# picaxe_prog_breakout.net
KiCad netlist of a schematic drawn in EAGLE
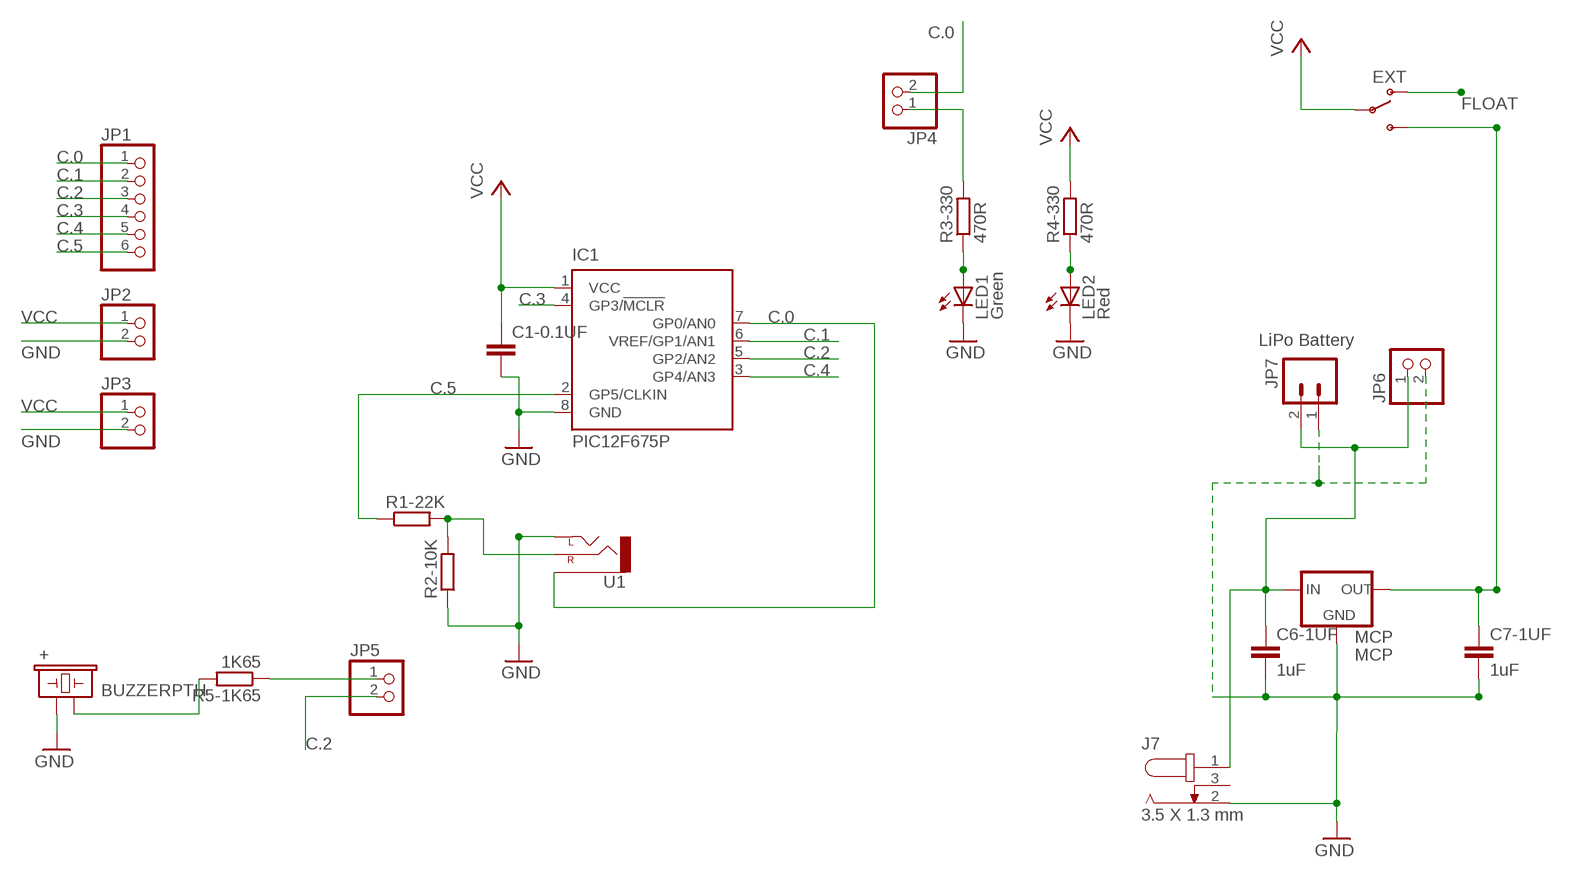
[diagram p0: schematic, sheet 1]

(export (version "E")
  (design (tool "Eeschema 10.0.6"))
  (components
    (comp (ref "+")
      (value "BUZZERPTH")
      (footprint "eagle-import:BUZZER-12MM")
      (libsource (lib "eagle-import") (part "BUZZERPTH"))
    )
    (comp (ref "C1-0.1UF")
      (value "C-EU025-025X050")
      (footprint "eagle-import:C025-025X050")
      (libsource (lib "eagle-import") (part "C-EU025-025X050"))
    )
    (comp (ref "C6-1UF")
      (value "1uF")
      (footprint "eagle-import:C050-025X075")
      (libsource (lib "eagle-import") (part "C-EU050-025X075"))
    )
    (comp (ref "C7-1UF")
      (value "1uF")
      (footprint "eagle-import:C050-025X075")
      (libsource (lib "eagle-import") (part "C-EU050-025X075"))
    )
    (comp (ref "IC1")
      (value "PIC12F675P")
      (footprint "eagle-import:DIL8")
      (fields (field (name "MF") "MICROCHIP") (field (name "MPN") "PIC12F675-E/P"))
      (libsource (lib "eagle-import") (part "PIC12F675P"))
    )
    (comp (ref "J7")
      (value "3.5 X 1.3 mm")
      (footprint "eagle-import:3.5X1.3MM_DC_JACK")
      (libsource (lib "eagle-import") (part "DC_JACK_3.5X1.3MM"))
    )
    (comp (ref "JP1")
      (value "PINHD-1X6")
      (footprint "eagle-import:1X06")
      (libsource (lib "eagle-import") (part "PINHD-1X6"))
    )
    (comp (ref "JP2")
      (value "PINHD-1X2")
      (footprint "eagle-import:1X02")
      (libsource (lib "eagle-import") (part "PINHD-1X2"))
    )
    (comp (ref "JP3")
      (value "PINHD-1X2")
      (footprint "eagle-import:1X02")
      (libsource (lib "eagle-import") (part "PINHD-1X2"))
    )
    (comp (ref "JP4")
      (value "PINHD-1X2")
      (footprint "eagle-import:1X02")
      (libsource (lib "eagle-import") (part "PINHD-1X2"))
    )
    (comp (ref "JP5")
      (value "PINHD-1X2")
      (footprint "eagle-import:1X02")
      (libsource (lib "eagle-import") (part "PINHD-1X2"))
    )
    (comp (ref "JP6")
      (value "PINHD-1X2")
      (footprint "eagle-import:1X02")
      (libsource (lib "eagle-import") (part "PINHD-1X2"))
    )
    (comp (ref "JP7")
      (value "LiPo Battery")
      (footprint "eagle-import:JST-2-PTH")
      (libsource (lib "eagle-import") (part "M02JST-PTH-2"))
    )
    (comp (ref "LED1")
      (value "Green")
      (footprint "eagle-import:LED3MM")
      (libsource (lib "eagle-import") (part "LED3MM"))
    )
    (comp (ref "LED2")
      (value "Red")
      (footprint "eagle-import:LED3MM")
      (libsource (lib "eagle-import") (part "LED3MM"))
    )
    (comp (ref "MCP")
      (value "MCP")
      (footprint "eagle-import:TO92-")
      (libsource (lib "eagle-import") (part "MCP1700TO-92"))
    )
    (comp (ref "ON")
      (value "EXT")
      (footprint "eagle-import:SWITCH-SPDT")
      (libsource (lib "eagle-import") (part "SWITCH-SPSTPTH"))
    )
    (comp (ref "R1-22K")
      (value "R-EU_0207/10")
      (footprint "eagle-import:0207_10")
      (libsource (lib "eagle-import") (part "R-EU_0207/10"))
    )
    (comp (ref "R2-10K")
      (value "R-EU_0207/10")
      (footprint "eagle-import:0207_10")
      (libsource (lib "eagle-import") (part "R-EU_0207/10"))
    )
    (comp (ref "R3-330")
      (value "470R")
      (footprint "eagle-import:0207_10")
      (libsource (lib "eagle-import") (part "R-EU_0207/10"))
    )
    (comp (ref "R4-330")
      (value "470R")
      (footprint "eagle-import:0207_10")
      (libsource (lib "eagle-import") (part "R-EU_0207/10"))
    )
    (comp (ref "R5-1K65")
      (value "1K65")
      (footprint "eagle-import:0207_10")
      (libsource (lib "eagle-import") (part "R-EU_0207/10"))
    )
    (comp (ref "U1")
      (value "AUDIO-JACKPTH")
      (footprint "eagle-import:AUDIO-JACK")
      (libsource (lib "eagle-import") (part "AUDIO-JACKPTH"))
    )
  )
  (nets
    (net (code "1") (name "/C.0") (class "Default")
      (node (ref "IC1") (pin "7") (pinfunction "GP0/AN0_7") (pintype "bidirectional"))
      (node (ref "JP1") (pin "1") (pinfunction "1_1") (pintype "passive"))
      (node (ref "JP4") (pin "2") (pinfunction "2_2") (pintype "passive"))
      (node (ref "U1") (pin "SLEEVE") (pinfunction "SLEEVE_SLEEVE") (pintype "bidirectional"))
    )
    (net (code "2") (name "/C.1") (class "Default")
      (node (ref "IC1") (pin "6") (pinfunction "VREF/GP1/AN1_6") (pintype "bidirectional"))
      (node (ref "JP1") (pin "2") (pinfunction "2_2") (pintype "passive"))
    )
    (net (code "3") (name "/C.2") (class "Default")
      (node (ref "IC1") (pin "5") (pinfunction "GP2/AN2_5") (pintype "bidirectional"))
      (node (ref "JP1") (pin "3") (pinfunction "3_3") (pintype "passive"))
      (node (ref "JP5") (pin "2") (pinfunction "2_2") (pintype "passive"))
    )
    (net (code "4") (name "/C.3") (class "Default")
      (node (ref "IC1") (pin "4") (pinfunction "GP3/~{MCLR}_4") (pintype "input"))
      (node (ref "JP1") (pin "4") (pinfunction "4_4") (pintype "passive"))
    )
    (net (code "5") (name "/C.4") (class "Default")
      (node (ref "IC1") (pin "3") (pinfunction "GP4/AN3_3") (pintype "bidirectional"))
      (node (ref "JP1") (pin "5") (pinfunction "5_5") (pintype "passive"))
    )
    (net (code "6") (name "/C.5") (class "Default")
      (node (ref "IC1") (pin "2") (pinfunction "GP5/CLKIN_2") (pintype "bidirectional"))
      (node (ref "JP1") (pin "6") (pinfunction "6_6") (pintype "passive"))
      (node (ref "R1-22K") (pin "1") (pinfunction "1_1") (pintype "passive"))
    )
    (net (code "7") (name "/FLOAT") (class "Default")
      (node (ref "ON") (pin "1") (pinfunction "O_1") (pintype "passive"))
    )
    (net (code "8") (name "GND") (class "Default")
      (node (ref "+") (pin "+") (pinfunction "1_+") (pintype "passive"))
      (node (ref "C1-0.1UF") (pin "2") (pinfunction "2_2") (pintype "passive"))
      (node (ref "C6-1UF") (pin "2") (pinfunction "2_2") (pintype "passive"))
      (node (ref "C7-1UF") (pin "2") (pinfunction "2_2") (pintype "passive"))
      (node (ref "IC1") (pin "8") (pinfunction "GND_8") (pintype "power_in"))
      (node (ref "J7") (pin "2") (pinfunction "2_2") (pintype "passive"))
      (node (ref "JP2") (pin "2") (pinfunction "2_2") (pintype "passive"))
      (node (ref "JP3") (pin "2") (pinfunction "2_2") (pintype "passive"))
      (node (ref "JP6") (pin "2") (pinfunction "2_2") (pintype "passive"))
      (node (ref "JP7") (pin "1") (pinfunction "1_1") (pintype "passive"))
      (node (ref "LED1") (pin "K") (pinfunction "C_K") (pintype "passive"))
      (node (ref "LED2") (pin "K") (pinfunction "C_K") (pintype "passive"))
      (node (ref "MCP") (pin "3") (pinfunction "GND_3") (pintype "input"))
      (node (ref "R2-10K") (pin "1") (pinfunction "1_1") (pintype "passive"))
      (node (ref "U1") (pin "TIP") (pinfunction "LEFT_TIP") (pintype "bidirectional"))
    )
    (net (code "9") (name "Net-(+-2)") (class "Default")
      (node (ref "+") (pin "-") (pinfunction "2_-") (pintype "passive"))
      (node (ref "R5-1K65") (pin "2") (pinfunction "2_2") (pintype "passive"))
    )
    (net (code "10") (name "Net-(JP4-Pad1)") (class "Default")
      (node (ref "JP4") (pin "1") (pinfunction "1_1") (pintype "passive"))
      (node (ref "R3-330") (pin "2") (pinfunction "2_2") (pintype "passive"))
    )
    (net (code "11") (name "Net-(JP5-Pad1)") (class "Default")
      (node (ref "JP5") (pin "1") (pinfunction "1_1") (pintype "passive"))
      (node (ref "R5-1K65") (pin "1") (pinfunction "1_1") (pintype "passive"))
    )
    (net (code "12") (name "Net-(LED1-PadA)") (class "Default")
      (node (ref "LED1") (pin "A") (pinfunction "A_A") (pintype "passive"))
      (node (ref "R3-330") (pin "1") (pinfunction "1_1") (pintype "passive"))
    )
    (net (code "13") (name "Net-(LED2-PadA)") (class "Default")
      (node (ref "LED2") (pin "A") (pinfunction "A_A") (pintype "passive"))
      (node (ref "R4-330") (pin "1") (pinfunction "1_1") (pintype "passive"))
    )
    (net (code "14") (name "Net-(MCP-IN)") (class "Default")
      (node (ref "C6-1UF") (pin "1") (pinfunction "1_1") (pintype "passive"))
      (node (ref "J7") (pin "1") (pinfunction "1_1") (pintype "passive"))
      (node (ref "JP6") (pin "1") (pinfunction "1_1") (pintype "passive"))
      (node (ref "JP7") (pin "2") (pinfunction "2_2") (pintype "passive"))
      (node (ref "MCP") (pin "2") (pinfunction "IN_2") (pintype "input"))
    )
    (net (code "15") (name "Net-(MCP-OUT)") (class "Default")
      (node (ref "C7-1UF") (pin "1") (pinfunction "1_1") (pintype "passive"))
      (node (ref "MCP") (pin "1") (pinfunction "OUT_1") (pintype "passive"))
      (node (ref "ON") (pin "3") (pinfunction "S_3") (pintype "passive"))
    )
    (net (code "16") (name "Net-(U1-RIGHT)") (class "Default")
      (node (ref "R1-22K") (pin "2") (pinfunction "2_2") (pintype "passive"))
      (node (ref "R2-10K") (pin "2") (pinfunction "2_2") (pintype "passive"))
      (node (ref "U1") (pin "RING") (pinfunction "RIGHT_RING") (pintype "bidirectional"))
    )
    (net (code "17") (name "VCC") (class "Default")
      (node (ref "C1-0.1UF") (pin "1") (pinfunction "1_1") (pintype "passive"))
      (node (ref "IC1") (pin "1") (pinfunction "VCC_1") (pintype "power_in"))
      (node (ref "JP2") (pin "1") (pinfunction "1_1") (pintype "passive"))
      (node (ref "JP3") (pin "1") (pinfunction "1_1") (pintype "passive"))
      (node (ref "ON") (pin "2") (pinfunction "P_2") (pintype "passive"))
      (node (ref "R4-330") (pin "2") (pinfunction "2_2") (pintype "passive"))
    )
    (net (code "18") (name "unconnected-(J7-Pad3)") (class "Default")
      (node (ref "J7") (pin "3") (pinfunction "3_3") (pintype "passive"))
    )
  )
)
